# BG1094_USB.net
KiCad netlist of a schematic drawn in Altium Designer
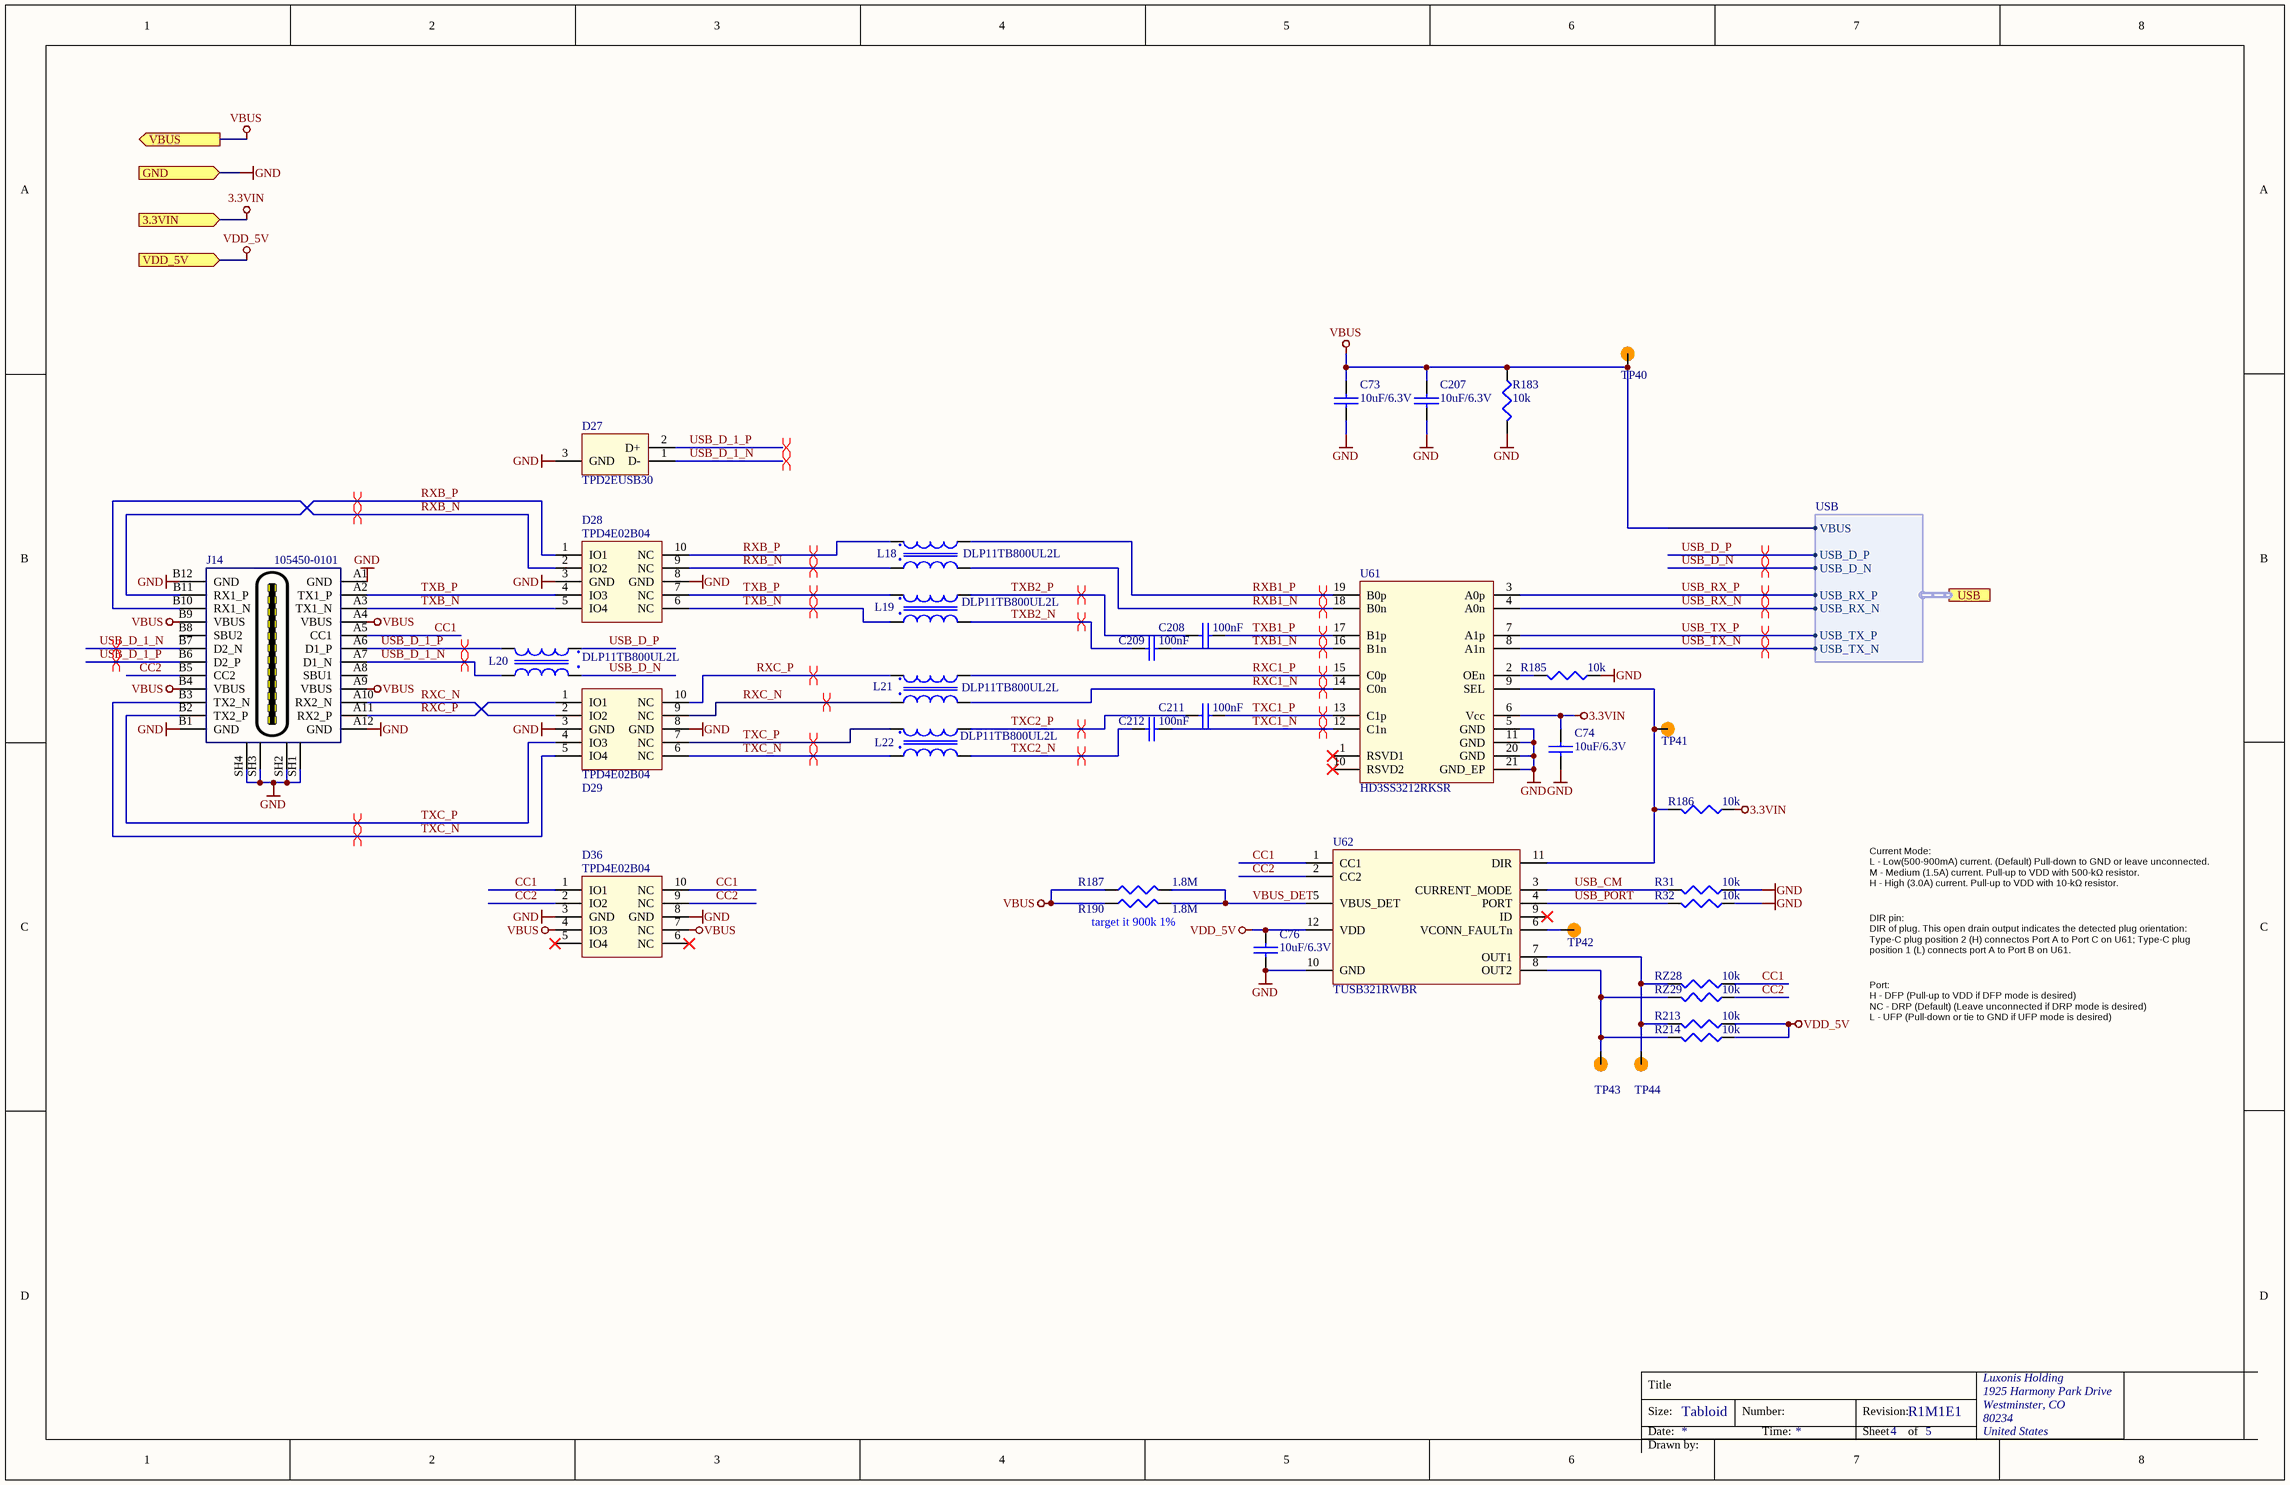
[diagram p0: BG1094_USB.SchDoc]

(export (version "E")
  (design (tool "Eeschema 10.0.6"))
  (components
    (comp (ref "C73")
      (value "10uF/6.3V")
      (footprint "CAPC0402(1005)70_N")
      (description "SMD Multilayer Ceramic Capacitor, 0402 [1005 Metric], 10 µF, 6.3 V, ± 20%, X5R")
      (libsource (lib "MV0235_R4M0E0") (part "CAP"))
    )
    (comp (ref "C74")
      (value "10uF/6.3V")
      (footprint "CAPC0402(1005)70_N")
      (description "SMD Multilayer Ceramic Capacitor, 0402 [1005 Metric], 10 µF, 6.3 V, ± 20%, X5R")
      (libsource (lib "MV0235_R4M0E0") (part "CAP"))
    )
    (comp (ref "C76")
      (value "10uF/6.3V")
      (footprint "CAPC0402(1005)70_N")
      (description "SMD Multilayer Ceramic Capacitor, 0402 [1005 Metric], 10 µF, 6.3 V, ± 20%, X5R")
      (libsource (lib "MV0235_R4M0E0") (part "CAP"))
    )
    (comp (ref "C207")
      (value "10uF/6.3V")
      (footprint "CAPC0402(1005)70_N")
      (description "SMD Multilayer Ceramic Capacitor, 0402 [1005 Metric], 10 µF, 6.3 V, ± 20%, X5R")
      (libsource (lib "MV0235_R4M0E0") (part "CAP"))
    )
    (comp (ref "C208")
      (value "100nF")
      (footprint "CAPC0201(0603)33_L")
      (description "SMD Multilayer Ceramic Capacitor, 0201 [0603 Metric], 0.1 µF, 6.3 V, ± 10%, X5R")
      (libsource (lib "MV0235_R1M0E0") (part "CAP"))
    )
    (comp (ref "C209")
      (value "100nF")
      (footprint "CAPC0201(0603)33_L")
      (description "SMD Multilayer Ceramic Capacitor, 0201 [0603 Metric], 0.1 µF, 6.3 V, ± 10%, X5R")
      (libsource (lib "MV0235_R1M0E0") (part "CAP"))
    )
    (comp (ref "C211")
      (value "100nF")
      (footprint "CAPC0201(0603)33_L")
      (description "SMD Multilayer Ceramic Capacitor, 0201 [0603 Metric], 0.1 µF, 6.3 V, ± 10%, X5R")
      (libsource (lib "MV0235_R1M0E0") (part "CAP"))
    )
    (comp (ref "C212")
      (value "100nF")
      (footprint "CAPC0201(0603)33_L")
      (description "SMD Multilayer Ceramic Capacitor, 0201 [0603 Metric], 0.1 µF, 6.3 V, ± 10%, X5R")
      (libsource (lib "MV0235_R1M0E0") (part "CAP"))
    )
    (comp (ref "D27")
      (value "TPD2EUSB30")
      (footprint "Luxonis:SOT-3")
      (description "DIODE, ESD, DUAL, USB3.0, SOT-3")
      (libsource (lib "Myriad2") (part "TPD2EUSB30"))
    )
    (comp (ref "D28")
      (value "TPD4E02B04")
      (footprint "Luxonis:DQA-10")
      (description "TVS DIODE 3.6VWM 8.8VC 10USON")
      (libsource (lib "MV0248_R0M0E0") (part "TPD4E02B04"))
    )
    (comp (ref "D29")
      (value "TPD4E02B04")
      (footprint "Luxonis:DQA-10")
      (description "TVS DIODE 3.6VWM 8.8VC 10USON")
      (libsource (lib "MV0248_R0M0E0") (part "TPD4E02B04"))
    )
    (comp (ref "D36")
      (value "TPD4E02B04")
      (footprint "Luxonis:DQA-10")
      (description "TVS DIODE 3.6VWM 8.8VC 10USON")
      (libsource (lib "MV0248_R0M0E0") (part "TPD4E02B04"))
    )
    (comp (ref "J14")
      (value "105450-0101")
      (footprint "Luxonis:Molex_105450-0101")
      (description "USB 3.1 Type C Receptacle SMD RA")
      (libsource (lib "MyriadX_D") (part "Molex_1054500101"))
    )
    (comp (ref "L18")
      (value "DLP11TB800UL2L")
      (footprint "Luxonis:CHOKE_0504")
      (description "CMC 150MA 2LN 80 OHM SMD")
      (libsource (lib "") (part "DLP11TB800UL2L_1"))
    )
    (comp (ref "L19")
      (value "DLP11TB800UL2L")
      (footprint "Luxonis:CHOKE_0504")
      (description "CMC 150MA 2LN 80 OHM SMD")
      (libsource (lib "") (part "DLP11TB800UL2L_1"))
    )
    (comp (ref "L20")
      (value "DLP11TB800UL2L")
      (footprint "Luxonis:CHOKE_0504")
      (description "CMC 150MA 2LN 80 OHM SMD")
      (libsource (lib "MyriadX_D") (part "DLP11TB800UL2L"))
    )
    (comp (ref "L21")
      (value "DLP11TB800UL2L")
      (footprint "Luxonis:CHOKE_0504")
      (description "CMC 150MA 2LN 80 OHM SMD")
      (libsource (lib "") (part "DLP11TB800UL2L_1"))
    )
    (comp (ref "L22")
      (value "DLP11TB800UL2L")
      (footprint "Luxonis:CHOKE_0504")
      (description "CMC 150MA 2LN 80 OHM SMD")
      (libsource (lib "") (part "DLP11TB800UL2L_1"))
    )
    (comp (ref "R31")
      (value "10k")
      (footprint "RESC0402(1005)_N")
      (description "SMD Chip Resistor, Thick Film, 10 kohm, 50 V, 0402, 100mW, ± 1%")
      (libsource (lib "MV0235_R4M0E0") (part "RES1"))
    )
    (comp (ref "R32")
      (value "10k")
      (footprint "RESC0402(1005)_N")
      (description "SMD Chip Resistor, Thick Film, 10 kohm, 50 V, 0402, 100mW, ± 1%")
      (libsource (lib "MV0235_R4M0E0") (part "RES1"))
    )
    (comp (ref "R183")
      (value "10k")
      (footprint "RESC0402(1005)_N")
      (description "SMD Chip Resistor, Thick Film, 10 kohm, 50 V, 0402, 100mW, ± 1%")
      (libsource (lib "MV0235_R4M0E0") (part "RES1"))
    )
    (comp (ref "R185")
      (value "10k")
      (footprint "RESC0402(1005)_N")
      (description "SMD Chip Resistor, Thick Film, 10 kohm, 50 V, 0402, 100mW, ± 1%")
      (libsource (lib "MV0235_R4M0E0") (part "RES1"))
    )
    (comp (ref "R186")
      (value "10k")
      (footprint "RESC0402(1005)_N")
      (description "SMD Chip Resistor, Thick Film, 10 kohm, 50 V, 0402, 100mW, ± 1%")
      (libsource (lib "MV0235_R4M0E0") (part "RES1"))
    )
    (comp (ref "R187")
      (value "1.8M")
      (footprint "IPC_RES_CAP:RESC0402(1005)_N")
      (description "RES SMD 1.8M 1% 0402 50V")
      (libsource (lib "MyriadX_D") (part "R_1.8M_1%_0402"))
    )
    (comp (ref "R190")
      (value "1.8M")
      (footprint "IPC_RES_CAP:RESC0402(1005)_N")
      (description "RES SMD 1.8M 1% 0402 50V")
      (libsource (lib "MyriadX_D") (part "R_1.8M_1%_0402"))
    )
    (comp (ref "R213")
      (value "10k")
      (footprint "RESC0402(1005)_N")
      (description "SMD Chip Resistor, Thick Film, 10 kohm, 50 V, 0402, 100mW, ± 1%")
      (libsource (lib "MV0235_R4M0E0") (part "RES1"))
    )
    (comp (ref "R214")
      (value "10k")
      (footprint "RESC0402(1005)_N")
      (description "SMD Chip Resistor, Thick Film, 10 kohm, 50 V, 0402, 100mW, ± 1%")
      (libsource (lib "MV0235_R4M0E0") (part "RES1"))
    )
    (comp (ref "RZ28")
      (value "10k")
      (footprint "RESC0402(1005)_N")
      (description "SMD Chip Resistor, Thick Film, 10 kohm, 50 V, 0402, 100mW, ± 1%")
      (libsource (lib "MV0235_R4M0E0") (part "RES1"))
    )
    (comp (ref "RZ29")
      (value "10k")
      (footprint "RESC0402(1005)_N")
      (description "SMD Chip Resistor, Thick Film, 10 kohm, 50 V, 0402, 100mW, ± 1%")
      (libsource (lib "MV0235_R4M0E0") (part "RES1"))
    )
    (comp (ref "TP40")
      (value "TP_SMD")
      (footprint "TP_0.75MM_SMD_NO-SILK")
      (description "circular pad test point, SMD")
      (libsource (lib "Luxonis") (part "TP_SMD"))
    )
    (comp (ref "TP41")
      (value "TP_SMD")
      (footprint "TP_0.75MM_SMD_NO-SILK")
      (description "circular pad test point, SMD")
      (libsource (lib "Luxonis") (part "TP_SMD"))
    )
    (comp (ref "TP42")
      (value "TP_SMD")
      (footprint "TP_0.75MM_SMD_NO-SILK")
      (description "circular pad test point, SMD")
      (libsource (lib "Luxonis") (part "TP_SMD"))
    )
    (comp (ref "TP43")
      (value "TP_SMD")
      (footprint "TP_0.75MM_SMD_NO-SILK")
      (description "circular pad test point, SMD")
      (libsource (lib "Luxonis") (part "TP_SMD"))
    )
    (comp (ref "TP44")
      (value "TP_SMD")
      (footprint "TP_0.75MM_SMD_NO-SILK")
      (description "circular pad test point, SMD")
      (libsource (lib "Luxonis") (part "TP_SMD"))
    )
    (comp (ref "U61")
      (value "HD3SS3212RKSR")
      (footprint "Luxonis:VQFN-20")
      (description "Two Channel Differential 2:1/1:2 10Gbps Mux/Demux")
      (libsource (lib "MyriadX_D") (part "HD3SS3212RKSR"))
    )
    (comp (ref "U62")
      (value "TUSB321RWBR")
      (footprint "Luxonis:X2QFN-12")
      (description "USB Type-C  ™ Configuration  Channel  Logic and Port Control  with VCONN")
      (libsource (lib "MyriadX_D") (part "TUSB321RWBR"))
    )
  )
  (nets
    (net (code "2") (name "/CC1") (class "Default")
      (node (ref "D36") (pin "1") (pinfunction "IO1_1") (pintype "passive"))
      (node (ref "D36") (pin "10") (pinfunction "NC_10") (pintype "passive"))
      (node (ref "J14") (pin "A5") (pinfunction "CC1_A5") (pintype "passive"))
      (node (ref "RZ28") (pin "1") (pintype "passive"))
      (node (ref "U62") (pin "1") (pinfunction "CC1_1") (pintype "passive"))
    )
    (net (code "3") (name "/CC2") (class "Default")
      (node (ref "D36") (pin "2") (pinfunction "IO2_2") (pintype "passive"))
      (node (ref "D36") (pin "9") (pinfunction "NC_9") (pintype "passive"))
      (node (ref "J14") (pin "B5") (pinfunction "CC2_B5") (pintype "passive"))
      (node (ref "RZ29") (pin "1") (pintype "passive"))
      (node (ref "U62") (pin "2") (pinfunction "CC2_2") (pintype "passive"))
    )
    (net (code "4") (name "/RXB1_N") (class "Default")
      (node (ref "L18") (pin "4") (pinfunction "4_4") (pintype "passive"))
      (node (ref "U61") (pin "18") (pinfunction "B0n_18") (pintype "passive"))
    )
    (net (code "5") (name "/RXB1_P") (class "Default")
      (node (ref "L18") (pin "2") (pinfunction "2_2") (pintype "passive"))
      (node (ref "U61") (pin "19") (pinfunction "B0p_19") (pintype "passive"))
    )
    (net (code "6") (name "/RXB_N") (class "Default")
      (node (ref "D28") (pin "2") (pinfunction "IO2_2") (pintype "passive"))
      (node (ref "D28") (pin "9") (pinfunction "NC_9") (pintype "passive"))
      (node (ref "J14") (pin "B10") (pinfunction "RX1_N_B10") (pintype "passive"))
      (node (ref "L18") (pin "3") (pinfunction "3_3") (pintype "passive"))
    )
    (net (code "7") (name "/RXB_P") (class "Default")
      (node (ref "D28") (pin "1") (pinfunction "IO1_1") (pintype "passive"))
      (node (ref "D28") (pin "10") (pinfunction "NC_10") (pintype "passive"))
      (node (ref "J14") (pin "B11") (pinfunction "RX1_P_B11") (pintype "passive"))
      (node (ref "L18") (pin "1") (pinfunction "1_1") (pintype "passive"))
    )
    (net (code "8") (name "/RXC1_N") (class "Default")
      (node (ref "L21") (pin "4") (pinfunction "4_4") (pintype "passive"))
      (node (ref "U61") (pin "14") (pinfunction "C0n_14") (pintype "passive"))
    )
    (net (code "9") (name "/RXC1_P") (class "Default")
      (node (ref "L21") (pin "2") (pinfunction "2_2") (pintype "passive"))
      (node (ref "U61") (pin "15") (pinfunction "C0p_15") (pintype "passive"))
    )
    (net (code "10") (name "/RXC_N") (class "Default")
      (node (ref "D29") (pin "2") (pinfunction "IO2_2") (pintype "passive"))
      (node (ref "D29") (pin "9") (pinfunction "NC_9") (pintype "passive"))
      (node (ref "J14") (pin "A10") (pinfunction "RX2_N_A10") (pintype "passive"))
      (node (ref "L21") (pin "3") (pinfunction "3_3") (pintype "passive"))
    )
    (net (code "11") (name "/RXC_P") (class "Default")
      (node (ref "D29") (pin "1") (pinfunction "IO1_1") (pintype "passive"))
      (node (ref "D29") (pin "10") (pinfunction "NC_10") (pintype "passive"))
      (node (ref "J14") (pin "A11") (pinfunction "RX2_P_A11") (pintype "passive"))
      (node (ref "L21") (pin "1") (pinfunction "1_1") (pintype "passive"))
    )
    (net (code "12") (name "/TXB1_N") (class "Default")
      (node (ref "C209") (pin "1") (pinfunction "1_1") (pintype "passive"))
      (node (ref "U61") (pin "16") (pinfunction "B1n_16") (pintype "passive"))
    )
    (net (code "13") (name "/TXB1_P") (class "Default")
      (node (ref "C208") (pin "1") (pinfunction "1_1") (pintype "passive"))
      (node (ref "U61") (pin "17") (pinfunction "B1p_17") (pintype "passive"))
    )
    (net (code "14") (name "/TXB2_N") (class "Default")
      (node (ref "C209") (pin "2") (pinfunction "2_2") (pintype "passive"))
      (node (ref "L19") (pin "4") (pinfunction "4_4") (pintype "passive"))
    )
    (net (code "15") (name "/TXB2_P") (class "Default")
      (node (ref "C208") (pin "2") (pinfunction "2_2") (pintype "passive"))
      (node (ref "L19") (pin "2") (pinfunction "2_2") (pintype "passive"))
    )
    (net (code "16") (name "/TXB_N") (class "Default")
      (node (ref "D28") (pin "5") (pinfunction "IO4_5") (pintype "passive"))
      (node (ref "D28") (pin "6") (pinfunction "NC_6") (pintype "passive"))
      (node (ref "J14") (pin "A3") (pinfunction "TX1_N_A3") (pintype "passive"))
      (node (ref "L19") (pin "3") (pinfunction "3_3") (pintype "passive"))
    )
    (net (code "17") (name "/TXB_P") (class "Default")
      (node (ref "D28") (pin "4") (pinfunction "IO3_4") (pintype "passive"))
      (node (ref "D28") (pin "7") (pinfunction "NC_7") (pintype "passive"))
      (node (ref "J14") (pin "A2") (pinfunction "TX1_P_A2") (pintype "passive"))
      (node (ref "L19") (pin "1") (pinfunction "1_1") (pintype "passive"))
    )
    (net (code "18") (name "/TXC1_N") (class "Default")
      (node (ref "C212") (pin "1") (pinfunction "1_1") (pintype "passive"))
      (node (ref "U61") (pin "12") (pinfunction "C1n_12") (pintype "passive"))
    )
    (net (code "19") (name "/TXC1_P") (class "Default")
      (node (ref "C211") (pin "1") (pinfunction "1_1") (pintype "passive"))
      (node (ref "U61") (pin "13") (pinfunction "C1p_13") (pintype "passive"))
    )
    (net (code "20") (name "/TXC2_N") (class "Default")
      (node (ref "C212") (pin "2") (pinfunction "2_2") (pintype "passive"))
      (node (ref "L22") (pin "4") (pinfunction "4_4") (pintype "passive"))
    )
    (net (code "21") (name "/TXC2_P") (class "Default")
      (node (ref "C211") (pin "2") (pinfunction "2_2") (pintype "passive"))
      (node (ref "L22") (pin "2") (pinfunction "2_2") (pintype "passive"))
    )
    (net (code "22") (name "/TXC_N") (class "Default")
      (node (ref "D29") (pin "5") (pinfunction "IO4_5") (pintype "passive"))
      (node (ref "D29") (pin "6") (pinfunction "NC_6") (pintype "passive"))
      (node (ref "J14") (pin "B3") (pinfunction "TX2_N_B3") (pintype "passive"))
      (node (ref "L22") (pin "3") (pinfunction "3_3") (pintype "passive"))
    )
    (net (code "23") (name "/TXC_P") (class "Default")
      (node (ref "D29") (pin "4") (pinfunction "IO3_4") (pintype "passive"))
      (node (ref "D29") (pin "7") (pinfunction "NC_7") (pintype "passive"))
      (node (ref "J14") (pin "B2") (pinfunction "TX2_P_B2") (pintype "passive"))
      (node (ref "L22") (pin "1") (pinfunction "1_1") (pintype "passive"))
    )
    (net (code "24") (name "/USB_CM") (class "Default")
      (node (ref "R31") (pin "1") (pintype "passive"))
      (node (ref "U62") (pin "3") (pinfunction "CURRENT_MODE_3") (pintype "passive"))
    )
    (net (code "25") (name "/USB_D_1_N") (class "Default")
      (node (ref "D27") (pin "1") (pinfunction "D-_1") (pintype "passive"))
      (node (ref "J14") (pin "A7") (pinfunction "D1_N_A7") (pintype "passive"))
      (node (ref "J14") (pin "B7") (pinfunction "D2_N_B7") (pintype "passive"))
      (node (ref "L20") (pin "4") (pinfunction "4_4") (pintype "passive"))
    )
    (net (code "26") (name "/USB_D_1_P") (class "Default")
      (node (ref "D27") (pin "2") (pinfunction "D+_2") (pintype "passive"))
      (node (ref "J14") (pin "A6") (pinfunction "D1_P_A6") (pintype "passive"))
      (node (ref "J14") (pin "B6") (pinfunction "D2_P_B6") (pintype "passive"))
      (node (ref "L20") (pin "2") (pinfunction "2_2") (pintype "passive"))
    )
    (net (code "27") (name "/USB_D_N") (class "Default")
      (node (ref "L20") (pin "3") (pinfunction "3_3") (pintype "passive"))
    )
    (net (code "28") (name "/USB_D_P") (class "Default")
      (node (ref "L20") (pin "1") (pinfunction "1_1") (pintype "passive"))
    )
    (net (code "29") (name "/USB_PORT") (class "Default")
      (node (ref "R32") (pin "1") (pintype "passive"))
      (node (ref "U62") (pin "4") (pinfunction "PORT_4") (pintype "passive"))
    )
    (net (code "30") (name "/USB_RX_N") (class "Default")
      (node (ref "U61") (pin "4") (pinfunction "A0n_4") (pintype "passive"))
    )
    (net (code "31") (name "/USB_RX_P") (class "Default")
      (node (ref "U61") (pin "3") (pinfunction "A0p_3") (pintype "passive"))
    )
    (net (code "32") (name "/USB_TX_N") (class "Default")
      (node (ref "U61") (pin "8") (pinfunction "A1n_8") (pintype "passive"))
    )
    (net (code "33") (name "/USB_TX_P") (class "Default")
      (node (ref "U61") (pin "7") (pinfunction "A1p_7") (pintype "passive"))
    )
    (net (code "34") (name "/VBUS_DET") (class "Default")
      (node (ref "R187") (pin "1") (pintype "passive"))
      (node (ref "R190") (pin "1") (pintype "passive"))
      (node (ref "U62") (pin "5") (pinfunction "VBUS_DET_5") (pintype "passive"))
    )
    (net (code "36") (name "3.3VIN") (class "Default")
      (node (ref "C74") (pin "2") (pinfunction "2_2") (pintype "passive"))
      (node (ref "R186") (pin "2") (pintype "passive"))
      (node (ref "U61") (pin "6") (pinfunction "Vcc_6") (pintype "passive"))
    )
    (net (code "37") (name "GND") (class "Default")
      (node (ref "C207") (pin "1") (pinfunction "1_1") (pintype "passive"))
      (node (ref "C73") (pin "1") (pinfunction "1_1") (pintype "passive"))
      (node (ref "C74") (pin "1") (pinfunction "1_1") (pintype "passive"))
      (node (ref "C76") (pin "1") (pinfunction "1_1") (pintype "passive"))
      (node (ref "D27") (pin "3") (pinfunction "GND_3") (pintype "passive"))
      (node (ref "D28") (pin "3") (pinfunction "GND_3") (pintype "passive"))
      (node (ref "D28") (pin "8") (pinfunction "GND_8") (pintype "passive"))
      (node (ref "D29") (pin "3") (pinfunction "GND_3") (pintype "passive"))
      (node (ref "D29") (pin "8") (pinfunction "GND_8") (pintype "passive"))
      (node (ref "D36") (pin "3") (pinfunction "GND_3") (pintype "passive"))
      (node (ref "D36") (pin "8") (pinfunction "GND_8") (pintype "passive"))
      (node (ref "J14") (pin "A1") (pinfunction "GND_A1") (pintype "passive"))
      (node (ref "J14") (pin "A12") (pinfunction "GND_A12") (pintype "passive"))
      (node (ref "J14") (pin "B1") (pinfunction "GND_B1") (pintype "passive"))
      (node (ref "J14") (pin "B12") (pinfunction "GND_B12") (pintype "passive"))
      (node (ref "J14") (pin "SH1") (pinfunction "SH_SH1") (pintype "passive"))
      (node (ref "J14") (pin "SH2") (pinfunction "SH_SH2") (pintype "passive"))
      (node (ref "J14") (pin "SH3") (pinfunction "SH_SH3") (pintype "passive"))
      (node (ref "J14") (pin "SH4") (pinfunction "SH_SH4") (pintype "passive"))
      (node (ref "R183") (pin "1") (pintype "passive"))
      (node (ref "R185") (pin "2") (pintype "passive"))
      (node (ref "R31") (pin "2") (pintype "passive"))
      (node (ref "R32") (pin "2") (pintype "passive"))
      (node (ref "U61") (pin "11") (pinfunction "GND_11") (pintype "passive"))
      (node (ref "U61") (pin "20") (pinfunction "GND_20") (pintype "passive"))
      (node (ref "U61") (pin "21") (pinfunction "GND_EP_21") (pintype "passive"))
      (node (ref "U61") (pin "5") (pinfunction "GND_5") (pintype "passive"))
      (node (ref "U62") (pin "10") (pinfunction "GND_10") (pintype "passive"))
    )
    (net (code "38") (name "Net-(U61-OEn)") (class "Default")
      (node (ref "R185") (pin "1") (pintype "passive"))
      (node (ref "U61") (pin "2") (pinfunction "OEn_2") (pintype "passive"))
    )
    (net (code "39") (name "Net-(U61-SEL)") (class "Default")
      (node (ref "R186") (pin "1") (pintype "passive"))
      (node (ref "TP41") (pin "1") (pintype "passive"))
      (node (ref "U61") (pin "9") (pinfunction "SEL_9") (pintype "passive"))
      (node (ref "U62") (pin "11") (pinfunction "DIR_11") (pintype "passive"))
    )
    (net (code "40") (name "Net-(U62-OUT1)") (class "Default")
      (node (ref "R213") (pin "1") (pintype "passive"))
      (node (ref "RZ28") (pin "2") (pintype "passive"))
      (node (ref "TP44") (pin "1") (pintype "passive"))
      (node (ref "U62") (pin "7") (pinfunction "OUT1_7") (pintype "passive"))
    )
    (net (code "41") (name "Net-(U62-OUT2)") (class "Default")
      (node (ref "R214") (pin "1") (pintype "passive"))
      (node (ref "RZ29") (pin "2") (pintype "passive"))
      (node (ref "TP43") (pin "1") (pintype "passive"))
      (node (ref "U62") (pin "8") (pinfunction "OUT2_8") (pintype "passive"))
    )
    (net (code "42") (name "Net-(U62-VCONN_FAULTn)") (class "Default")
      (node (ref "TP42") (pin "1") (pintype "passive"))
      (node (ref "U62") (pin "6") (pinfunction "VCONN_FAULTn_6") (pintype "passive"))
    )
    (net (code "43") (name "VBUS") (class "Default")
      (node (ref "C207") (pin "2") (pinfunction "2_2") (pintype "passive"))
      (node (ref "C73") (pin "2") (pinfunction "2_2") (pintype "passive"))
      (node (ref "D36") (pin "4") (pinfunction "IO3_4") (pintype "passive"))
      (node (ref "D36") (pin "7") (pinfunction "NC_7") (pintype "passive"))
      (node (ref "J14") (pin "A4") (pinfunction "VBUS_A4") (pintype "passive"))
      (node (ref "J14") (pin "A9") (pinfunction "VBUS_A9") (pintype "passive"))
      (node (ref "J14") (pin "B4") (pinfunction "VBUS_B4") (pintype "passive"))
      (node (ref "J14") (pin "B9") (pinfunction "VBUS_B9") (pintype "passive"))
      (node (ref "R183") (pin "2") (pintype "passive"))
      (node (ref "R187") (pin "2") (pintype "passive"))
      (node (ref "R190") (pin "2") (pintype "passive"))
      (node (ref "TP40") (pin "1") (pintype "passive"))
    )
    (net (code "44") (name "VDD_5V") (class "Default")
      (node (ref "C76") (pin "2") (pinfunction "2_2") (pintype "passive"))
      (node (ref "R213") (pin "2") (pintype "passive"))
      (node (ref "R214") (pin "2") (pintype "passive"))
      (node (ref "U62") (pin "12") (pinfunction "VDD_12") (pintype "passive"))
    )
    (net (code "45") (name "unconnected-(D36-IO4-Pad5)") (class "Default")
      (node (ref "D36") (pin "5") (pinfunction "IO4_5") (pintype "passive+no_connect"))
    )
    (net (code "46") (name "unconnected-(D36-NC-Pad6)") (class "Default")
      (node (ref "D36") (pin "6") (pinfunction "NC_6") (pintype "passive+no_connect"))
    )
    (net (code "47") (name "unconnected-(J14-SBU1-PadA8)") (class "Default")
      (node (ref "J14") (pin "A8") (pinfunction "SBU1_A8") (pintype "passive"))
    )
    (net (code "48") (name "unconnected-(J14-SBU2-PadB8)") (class "Default")
      (node (ref "J14") (pin "B8") (pinfunction "SBU2_B8") (pintype "passive"))
    )
    (net (code "49") (name "unconnected-(U61-RSVD1-Pad1)") (class "Default")
      (node (ref "U61") (pin "1") (pinfunction "RSVD1_1") (pintype "passive+no_connect"))
    )
    (net (code "50") (name "unconnected-(U61-RSVD2-Pad10)") (class "Default")
      (node (ref "U61") (pin "10") (pinfunction "RSVD2_10") (pintype "passive+no_connect"))
    )
    (net (code "51") (name "unconnected-(U62-ID-Pad9)") (class "Default")
      (node (ref "U62") (pin "9") (pinfunction "ID_9") (pintype "passive+no_connect"))
    )
  )
)
